# Ethernet.net
KiCad netlist of a schematic drawn in Altium Designer
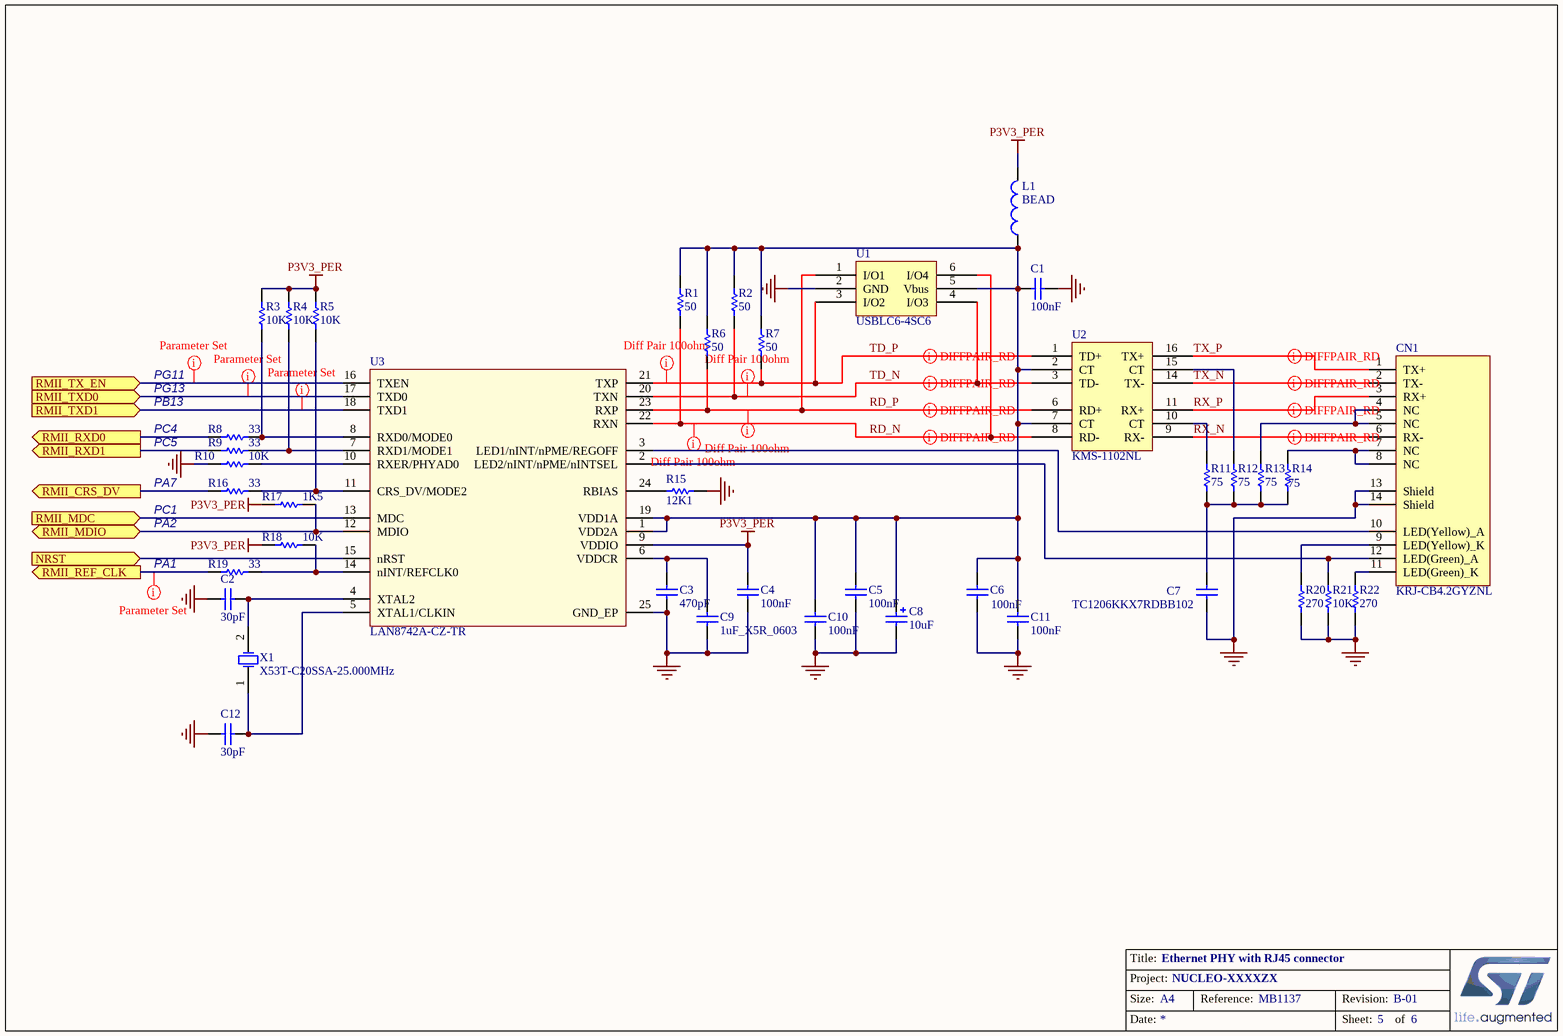
[diagram p0: Ethernet.SchDoc]

(export (version "E")
  (design (tool "Eeschema 10.0.6"))
  (components
    (comp (ref "C1")
      (value "100nF")
      (footprint "0603C")
      (description "Capacitor 0402 / 0603 / 0805")
      (libsource (lib "MCD_TOOLS") (part "Capacitor_ST"))
    )
    (comp (ref "C2")
      (value "30pF")
      (footprint "0603C")
      (description "Capacitor 0402 / 0603 / 0805")
      (libsource (lib "MCD_TOOLS") (part "Capacitor_ST"))
    )
    (comp (ref "C3")
      (value "470pF")
      (footprint "0603C")
      (description "Capacitor 0402 / 0603 / 0805")
      (libsource (lib "MCD_TOOLS") (part "Capacitor_ST"))
    )
    (comp (ref "C4")
      (value "100nF")
      (footprint "0603C")
      (description "Capacitor 0402 / 0603 / 0805")
      (libsource (lib "MCD_TOOLS") (part "Capacitor_ST"))
    )
    (comp (ref "C5")
      (value "100nF")
      (footprint "0603C")
      (description "Capacitor 0402 / 0603 / 0805")
      (libsource (lib "MCD_TOOLS") (part "Capacitor_ST"))
    )
    (comp (ref "C6")
      (value "100nF")
      (footprint "0603C")
      (description "Capacitor 0402 / 0603 / 0805")
      (libsource (lib "MCD_TOOLS") (part "Capacitor_ST"))
    )
    (comp (ref "C7")
      (value "TC1206KKX7RDBB102")
      (footprint "1206C")
      (description "Capacitor 0402 / 0603 / 0805/ 1206")
      (libsource (lib "MCD_TOOLS") (part "Capacitor_ST"))
    )
    (comp (ref "C8")
      (value "10uF")
      (footprint "TAN-A")
      (description "Polarized Capacitor,10uF,10V,10%,typeA,VISHAY")
      (libsource (lib "MCD_TOOLS") (part "Cap_10uF_POL_10%_TANA"))
    )
    (comp (ref "C9")
      (value "1uF_X5R_0603")
      (footprint "0603C")
      (description "0603  X5R 1µF")
      (fields (field (name "TOLERANCE") "10%"))
      (libsource (lib "MB963_1") (part "CAP SMD 0603  X5R 1µF 25V 10%"))
    )
    (comp (ref "C10")
      (value "100nF")
      (footprint "0603C")
      (description "Capacitor 0402 / 0603 / 0805")
      (libsource (lib "MCD_TOOLS") (part "Capacitor_ST"))
    )
    (comp (ref "C11")
      (value "100nF")
      (footprint "0603C")
      (description "Capacitor 0402 / 0603 / 0805")
      (libsource (lib "MCD_TOOLS") (part "Capacitor_ST"))
    )
    (comp (ref "C12")
      (value "30pF")
      (footprint "0603C")
      (description "Capacitor 0402 / 0603 / 0805")
      (libsource (lib "MCD_TOOLS") (part "Capacitor_ST"))
    )
    (comp (ref "CN1")
      (value "KRJ-CB4.2GYZNL")
      (footprint "RJ45_KRJ-CB4.2GYZNL")
      (description "100 Base-TX (Fast Ethernet) SMD RJ45 single port (1x1) with LEDS Integrated Magnetics Connector")
      (libsource (lib "MB1137") (part "KRJ-CB4.2GYZNL"))
    )
    (comp (ref "L1")
      (value "BEAD")
      (footprint "0603L")
      (description "Inductor")
      (fields (field (name "PUBLISHER") "Altium Limited"))
      (libsource (lib "Miscellaneous Devices") (part "Inductor"))
    )
    (comp (ref "R1")
      (value "50")
      (footprint "0603R")
      (description "Resistor,50,0603,1%,YAGEO")
      (libsource (lib "MB1137") (part "Res_50_1%_0603"))
    )
    (comp (ref "R2")
      (value "50")
      (footprint "0603R")
      (description "Resistor,50,0603,1%,YAGEO")
      (libsource (lib "MB1137") (part "Res_50_1%_0603"))
    )
    (comp (ref "R3")
      (value "10K")
      (footprint "0603R")
      (description "Resistor 0402 / 0603 / 0805")
      (libsource (lib "Miscellaneous Devices") (part "Res1"))
    )
    (comp (ref "R4")
      (value "10K")
      (footprint "0603R")
      (description "Resistor 0402 / 0603 / 0805")
      (libsource (lib "Miscellaneous Devices") (part "Res1"))
    )
    (comp (ref "R5")
      (value "10K")
      (footprint "0603R")
      (description "Resistor 0402 / 0603 / 0805")
      (libsource (lib "Miscellaneous Devices") (part "Res1"))
    )
    (comp (ref "R6")
      (value "50")
      (footprint "0603R")
      (description "Resistor,50,0603,1%,YAGEO")
      (libsource (lib "MB1137") (part "Res_50_1%_0603"))
    )
    (comp (ref "R7")
      (value "50")
      (footprint "0603R")
      (description "Resistor,50,0603,1%,YAGEO")
      (libsource (lib "MB1137") (part "Res_50_1%_0603"))
    )
    (comp (ref "R8")
      (value "33")
      (footprint "0603R")
      (description "Resistor,33,0402,1%,YAGEO")
      (libsource (lib "MCD_TOOLS") (part "Res_33_1%_0402"))
    )
    (comp (ref "R9")
      (value "33")
      (footprint "0603R")
      (description "Resistor,33,0402,1%,YAGEO")
      (libsource (lib "MCD_TOOLS") (part "Res_33_1%_0402"))
    )
    (comp (ref "R10")
      (value "10K")
      (footprint "0603R")
      (description "Resistor 0402 / 0603 / 0805")
      (libsource (lib "Miscellaneous Devices") (part "Res1"))
    )
    (comp (ref "R11")
      (value "75")
      (footprint "0603R")
      (description "Resistor,75,0603,1%,YAGEO")
      (libsource (lib "MB1137") (part "Res_75_1%_0603"))
    )
    (comp (ref "R12")
      (value "75")
      (footprint "0603R")
      (description "Resistor,75,0603,1%,YAGEO")
      (libsource (lib "MB1137") (part "Res_75_1%_0603"))
    )
    (comp (ref "R13")
      (value "75")
      (footprint "0603R")
      (description "Resistor,75,0603,1%,YAGEO")
      (libsource (lib "MB1137") (part "Res_75_1%_0603"))
    )
    (comp (ref "R14")
      (value "75")
      (footprint "0603R")
      (description "Resistor,75,0603,1%,YAGEO")
      (libsource (lib "MB1137") (part "Res_75_1%_0603"))
    )
    (comp (ref "R15")
      (value "12K1")
      (footprint "0603R")
      (description "Resistor,12K1,0603,1%,VISHAY")
      (libsource (lib "MCD_TOOLS") (part "Res_12K1_1%_0603"))
    )
    (comp (ref "R16")
      (value "33")
      (footprint "0603R")
      (description "Resistor,33,0402,1%,YAGEO")
      (libsource (lib "MCD_TOOLS") (part "Res_33_1%_0402"))
    )
    (comp (ref "R17")
      (value "1K5")
      (footprint "0603R")
      (description "Resistor,1K5,0402,1%,YAGEO")
      (libsource (lib "MCD_TOOLS") (part "Res_1K5_1%_0402"))
    )
    (comp (ref "R18")
      (value "10K")
      (footprint "0603R")
      (description "Resistor 0402 / 0603 / 0805")
      (libsource (lib "Miscellaneous Devices") (part "Res1"))
    )
    (comp (ref "R19")
      (value "33")
      (footprint "0603R")
      (description "Resistor,33,0402,1%,YAGEO")
      (libsource (lib "MCD_TOOLS") (part "Res_33_1%_0402"))
    )
    (comp (ref "R20")
      (value "270")
      (footprint "0603R")
      (description "Resistor 0402 / 0603 / 0805")
      (libsource (lib "Miscellaneous Devices") (part "Res1"))
    )
    (comp (ref "R21")
      (value "10K")
      (footprint "0603R")
      (description "Resistor 0402 / 0603 / 0805")
      (libsource (lib "Miscellaneous Devices") (part "Res1"))
    )
    (comp (ref "R22")
      (value "270")
      (footprint "0603R")
      (description "Resistor 0402 / 0603 / 0805")
      (libsource (lib "Miscellaneous Devices") (part "Res1"))
    )
    (comp (ref "U1")
      (value "USBLC6-4SC6")
      (footprint "SOT23-6L")
      (libsource (lib "MB1137_1") (part "USBLC6-4SC6"))
    )
    (comp (ref "U2")
      (value "KMS-1102NL")
      (footprint "Transformer")
      (libsource (lib "MB1137") (part "KMS-1102NL"))
    )
    (comp (ref "U3")
      (value "LAN8742A-CZ-TR")
      (footprint "QFN24_0R5_4X4")
      (libsource (lib "MB1137") (part "LAN8742A-CZ-TR"))
    )
    (comp (ref "X1")
      (value "X53T-C20SSA-25.000MHz")
      (footprint "XTAL_2SM_5R0X3R2")
      (description "Crystal Oscillator")
      (fields (field (name "PUBLISHER") "Altium Limited"))
      (libsource (lib "MB1137") (part "XTAL_5032"))
    )
  )
  (nets
    (net (code "1") (name "/NRST") (class "Default")
      (node (ref "U3") (pin "15") (pinfunction "nRST_15") (pintype "passive"))
    )
    (net (code "2") (name "/RD_N") (class "Default")
      (node (ref "R1") (pin "1") (pinfunction "1_1") (pintype "passive"))
      (node (ref "U1") (pin "6") (pinfunction "I/O4_6") (pintype "passive"))
      (node (ref "U2") (pin "8") (pinfunction "RD-_8") (pintype "passive"))
      (node (ref "U3") (pin "22") (pinfunction "RXN_22") (pintype "passive"))
    )
    (net (code "3") (name "/RD_P") (class "Default")
      (node (ref "R6") (pin "1") (pinfunction "1_1") (pintype "passive"))
      (node (ref "U1") (pin "1") (pinfunction "I/O1_1") (pintype "passive"))
      (node (ref "U2") (pin "6") (pinfunction "RD+_6") (pintype "passive"))
      (node (ref "U3") (pin "23") (pinfunction "RXP_23") (pintype "passive"))
    )
    (net (code "4") (name "/RMII_CRS_DV") (class "Default")
      (node (ref "R16") (pin "2") (pinfunction "2_2") (pintype "passive"))
    )
    (net (code "5") (name "/RMII_MDC") (class "Default")
      (node (ref "U3") (pin "13") (pinfunction "MDC_13") (pintype "passive"))
    )
    (net (code "6") (name "/RMII_MDIO") (class "Default")
      (node (ref "R17") (pin "1") (pinfunction "1_1") (pintype "passive"))
      (node (ref "U3") (pin "12") (pinfunction "MDIO_12") (pintype "passive"))
    )
    (net (code "7") (name "/RMII_REF_CLK") (class "Default")
      (node (ref "R19") (pin "2") (pinfunction "2_2") (pintype "passive"))
    )
    (net (code "8") (name "/RMII_RXD0") (class "Default")
      (node (ref "R8") (pin "2") (pinfunction "2_2") (pintype "passive"))
    )
    (net (code "9") (name "/RMII_RXD1") (class "Default")
      (node (ref "R9") (pin "2") (pinfunction "2_2") (pintype "passive"))
    )
    (net (code "10") (name "/RMII_TXD0") (class "Default")
      (node (ref "U3") (pin "17") (pinfunction "TXD0_17") (pintype "passive"))
    )
    (net (code "11") (name "/RMII_TXD1") (class "Default")
      (node (ref "U3") (pin "18") (pinfunction "TXD1_18") (pintype "passive"))
    )
    (net (code "12") (name "/RMII_TX_EN") (class "Default")
      (node (ref "U3") (pin "16") (pinfunction "TXEN_16") (pintype "passive"))
    )
    (net (code "13") (name "/RX_N") (class "Default")
      (node (ref "CN1") (pin "6") (pinfunction "RX-_6") (pintype "passive"))
      (node (ref "U2") (pin "9") (pinfunction "RX-_9") (pintype "passive"))
    )
    (net (code "14") (name "/RX_P") (class "Default")
      (node (ref "CN1") (pin "3") (pinfunction "RX+_3") (pintype "passive"))
      (node (ref "U2") (pin "11") (pinfunction "RX+_11") (pintype "passive"))
    )
    (net (code "15") (name "/TD_N") (class "Default")
      (node (ref "R2") (pin "1") (pinfunction "1_1") (pintype "passive"))
      (node (ref "U1") (pin "4") (pinfunction "I/O3_4") (pintype "passive"))
      (node (ref "U2") (pin "3") (pinfunction "TD-_3") (pintype "passive"))
      (node (ref "U3") (pin "20") (pinfunction "TXN_20") (pintype "passive"))
    )
    (net (code "16") (name "/TD_P") (class "Default")
      (node (ref "R7") (pin "1") (pinfunction "1_1") (pintype "passive"))
      (node (ref "U1") (pin "3") (pinfunction "I/O2_3") (pintype "passive"))
      (node (ref "U2") (pin "1") (pinfunction "TD+_1") (pintype "passive"))
      (node (ref "U3") (pin "21") (pinfunction "TXP_21") (pintype "passive"))
    )
    (net (code "17") (name "/TX_N") (class "Default")
      (node (ref "CN1") (pin "2") (pinfunction "TX-_2") (pintype "passive"))
      (node (ref "U2") (pin "14") (pinfunction "TX-_14") (pintype "passive"))
    )
    (net (code "18") (name "/TX_P") (class "Default")
      (node (ref "CN1") (pin "1") (pinfunction "TX+_1") (pintype "passive"))
      (node (ref "U2") (pin "16") (pinfunction "TX+_16") (pintype "passive"))
    )
    (net (code "19") (name "GND") (class "Default")
      (node (ref "C1") (pin "1") (pinfunction "1_1") (pintype "passive"))
      (node (ref "C10") (pin "1") (pinfunction "1_1") (pintype "passive"))
      (node (ref "C11") (pin "1") (pinfunction "1_1") (pintype "passive"))
      (node (ref "C12") (pin "2") (pinfunction "2_2") (pintype "passive"))
      (node (ref "C2") (pin "2") (pinfunction "2_2") (pintype "passive"))
      (node (ref "C3") (pin "1") (pinfunction "1_1") (pintype "passive"))
      (node (ref "C4") (pin "1") (pinfunction "1_1") (pintype "passive"))
      (node (ref "C5") (pin "1") (pinfunction "1_1") (pintype "passive"))
      (node (ref "C6") (pin "1") (pinfunction "1_1") (pintype "passive"))
      (node (ref "C7") (pin "1") (pinfunction "1_1") (pintype "passive"))
      (node (ref "C8") (pin "2") (pinfunction "2_2") (pintype "passive"))
      (node (ref "C9") (pin "2") (pinfunction "2_2") (pintype "passive"))
      (node (ref "CN1") (pin "13") (pinfunction "Shield_13") (pintype "passive"))
      (node (ref "CN1") (pin "14") (pinfunction "Shield_14") (pintype "passive"))
      (node (ref "R10") (pin "2") (pinfunction "2_2") (pintype "passive"))
      (node (ref "R15") (pin "2") (pinfunction "2_2") (pintype "passive"))
      (node (ref "R20") (pin "2") (pinfunction "2_2") (pintype "passive"))
      (node (ref "R21") (pin "2") (pinfunction "2_2") (pintype "passive"))
      (node (ref "R22") (pin "2") (pinfunction "2_2") (pintype "passive"))
      (node (ref "U1") (pin "2") (pinfunction "GND_2") (pintype "passive"))
      (node (ref "U3") (pin "25") (pinfunction "GND_EP_25") (pintype "passive"))
    )
    (net (code "20") (name "Net-(C7-Pad2)") (class "Default")
      (node (ref "C7") (pin "2") (pinfunction "2_2") (pintype "passive"))
      (node (ref "R11") (pin "1") (pinfunction "1_1") (pintype "passive"))
      (node (ref "R12") (pin "1") (pinfunction "1_1") (pintype "passive"))
      (node (ref "R13") (pin "1") (pinfunction "1_1") (pintype "passive"))
      (node (ref "R14") (pin "1") (pinfunction "1_1") (pintype "passive"))
    )
    (net (code "21") (name "Net-(CN1-LED(Green)_A)") (class "Default")
      (node (ref "CN1") (pin "12") (pinfunction "LED(Green)_A_12") (pintype "passive"))
      (node (ref "R21") (pin "1") (pinfunction "1_1") (pintype "passive"))
      (node (ref "U3") (pin "2") (pinfunction "LED2/nINT/nPME/nINTSEL_2") (pintype "passive"))
    )
    (net (code "22") (name "Net-(CN1-LED(Green)_K)") (class "Default")
      (node (ref "CN1") (pin "11") (pinfunction "LED(Green)_K_11") (pintype "passive"))
      (node (ref "R22") (pin "1") (pinfunction "1_1") (pintype "passive"))
    )
    (net (code "23") (name "Net-(CN1-LED(Yellow)_A)") (class "Default")
      (node (ref "CN1") (pin "10") (pinfunction "LED(Yellow)_A_10") (pintype "passive"))
      (node (ref "U3") (pin "3") (pinfunction "LED1/nINT/nPME/REGOFF_3") (pintype "passive"))
    )
    (net (code "24") (name "Net-(CN1-LED(Yellow)_K)") (class "Default")
      (node (ref "CN1") (pin "9") (pinfunction "LED(Yellow)_K_9") (pintype "passive"))
      (node (ref "R20") (pin "1") (pinfunction "1_1") (pintype "passive"))
    )
    (net (code "25") (name "Net-(CN1-NC-Pad4)") (class "Default")
      (node (ref "CN1") (pin "4") (pinfunction "NC_4") (pintype "passive"))
      (node (ref "CN1") (pin "5") (pinfunction "NC_5") (pintype "passive"))
      (node (ref "R13") (pin "2") (pinfunction "2_2") (pintype "passive"))
    )
    (net (code "26") (name "Net-(CN1-NC-Pad7)") (class "Default")
      (node (ref "CN1") (pin "7") (pinfunction "NC_7") (pintype "passive"))
      (node (ref "CN1") (pin "8") (pinfunction "NC_8") (pintype "passive"))
      (node (ref "R14") (pin "2") (pinfunction "2_2") (pintype "passive"))
    )
    (net (code "27") (name "Net-(R11-Pad2)") (class "Default")
      (node (ref "R11") (pin "2") (pinfunction "2_2") (pintype "passive"))
      (node (ref "U2") (pin "10") (pinfunction "CT_10") (pintype "passive"))
    )
    (net (code "28") (name "Net-(R12-Pad2)") (class "Default")
      (node (ref "R12") (pin "2") (pinfunction "2_2") (pintype "passive"))
      (node (ref "U2") (pin "15") (pinfunction "CT_15") (pintype "passive"))
    )
    (net (code "29") (name "Net-(U1-Vbus)") (class "Default")
      (node (ref "C1") (pin "2") (pinfunction "2_2") (pintype "passive"))
      (node (ref "C10") (pin "2") (pinfunction "2_2") (pintype "passive"))
      (node (ref "C11") (pin "2") (pinfunction "2_2") (pintype "passive"))
      (node (ref "C5") (pin "2") (pinfunction "2_2") (pintype "passive"))
      (node (ref "C6") (pin "2") (pinfunction "2_2") (pintype "passive"))
      (node (ref "C8") (pin "1") (pinfunction "1_1") (pintype "passive"))
      (node (ref "L1") (pin "1") (pinfunction "1_1") (pintype "passive"))
      (node (ref "R1") (pin "2") (pinfunction "2_2") (pintype "passive"))
      (node (ref "R2") (pin "2") (pinfunction "2_2") (pintype "passive"))
      (node (ref "R6") (pin "2") (pinfunction "2_2") (pintype "passive"))
      (node (ref "R7") (pin "2") (pinfunction "2_2") (pintype "passive"))
      (node (ref "U1") (pin "5") (pinfunction "Vbus_5") (pintype "passive"))
      (node (ref "U2") (pin "2") (pinfunction "CT_2") (pintype "passive"))
      (node (ref "U2") (pin "7") (pinfunction "CT_7") (pintype "passive"))
      (node (ref "U3") (pin "1") (pinfunction "VDD2A_1") (pintype "passive"))
      (node (ref "U3") (pin "19") (pinfunction "VDD1A_19") (pintype "passive"))
    )
    (net (code "30") (name "Net-(U3-CRS_DV{slash}MODE2)") (class "Default")
      (node (ref "R16") (pin "1") (pinfunction "1_1") (pintype "passive"))
      (node (ref "R5") (pin "2") (pinfunction "2_2") (pintype "passive"))
      (node (ref "U3") (pin "11") (pinfunction "CRS_DV/MODE2_11") (pintype "passive"))
    )
    (net (code "31") (name "Net-(U3-RBIAS)") (class "Default")
      (node (ref "R15") (pin "1") (pinfunction "1_1") (pintype "passive"))
      (node (ref "U3") (pin "24") (pinfunction "RBIAS_24") (pintype "passive"))
    )
    (net (code "32") (name "Net-(U3-RXD0{slash}MODE0)") (class "Default")
      (node (ref "R3") (pin "2") (pinfunction "2_2") (pintype "passive"))
      (node (ref "R8") (pin "1") (pinfunction "1_1") (pintype "passive"))
      (node (ref "U3") (pin "8") (pinfunction "RXD0/MODE0_8") (pintype "passive"))
    )
    (net (code "33") (name "Net-(U3-RXD1{slash}MODE1)") (class "Default")
      (node (ref "R4") (pin "2") (pinfunction "2_2") (pintype "passive"))
      (node (ref "R9") (pin "1") (pinfunction "1_1") (pintype "passive"))
      (node (ref "U3") (pin "7") (pinfunction "RXD1/MODE1_7") (pintype "passive"))
    )
    (net (code "34") (name "Net-(U3-RXER{slash}PHYAD0)") (class "Default")
      (node (ref "R10") (pin "1") (pinfunction "1_1") (pintype "passive"))
      (node (ref "U3") (pin "10") (pinfunction "RXER/PHYAD0_10") (pintype "passive"))
    )
    (net (code "35") (name "Net-(U3-VDDCR)") (class "Default")
      (node (ref "C3") (pin "2") (pinfunction "2_2") (pintype "passive"))
      (node (ref "C9") (pin "1") (pinfunction "1_1") (pintype "passive"))
      (node (ref "U3") (pin "6") (pinfunction "VDDCR_6") (pintype "passive"))
    )
    (net (code "36") (name "Net-(U3-XTAL1{slash}CLKIN)") (class "Default")
      (node (ref "C12") (pin "1") (pinfunction "1_1") (pintype "passive"))
      (node (ref "U3") (pin "5") (pinfunction "XTAL1/CLKIN_5") (pintype "passive"))
      (node (ref "X1") (pin "1") (pinfunction "OSC1_1") (pintype "passive"))
    )
    (net (code "37") (name "Net-(U3-XTAL2)") (class "Default")
      (node (ref "C2") (pin "1") (pinfunction "1_1") (pintype "passive"))
      (node (ref "U3") (pin "4") (pinfunction "XTAL2_4") (pintype "passive"))
      (node (ref "X1") (pin "2") (pinfunction "OSC2_2") (pintype "passive"))
    )
    (net (code "38") (name "Net-(U3-nINT{slash}REFCLK0)") (class "Default")
      (node (ref "R18") (pin "2") (pinfunction "2_2") (pintype "passive"))
      (node (ref "R19") (pin "1") (pinfunction "1_1") (pintype "passive"))
      (node (ref "U3") (pin "14") (pinfunction "nINT/REFCLK0_14") (pintype "passive"))
    )
    (net (code "39") (name "P3V3_PER") (class "Default")
      (node (ref "C4") (pin "2") (pinfunction "2_2") (pintype "passive"))
      (node (ref "L1") (pin "2") (pinfunction "2_2") (pintype "passive"))
      (node (ref "R17") (pin "2") (pinfunction "2_2") (pintype "passive"))
      (node (ref "R18") (pin "1") (pinfunction "1_1") (pintype "passive"))
      (node (ref "R3") (pin "1") (pinfunction "1_1") (pintype "passive"))
      (node (ref "R4") (pin "1") (pinfunction "1_1") (pintype "passive"))
      (node (ref "R5") (pin "1") (pinfunction "1_1") (pintype "passive"))
      (node (ref "U3") (pin "9") (pinfunction "VDDIO_9") (pintype "passive"))
    )
  )
)
